# stm32.net
KiCad netlist of a schematic drawn in Altium Designer
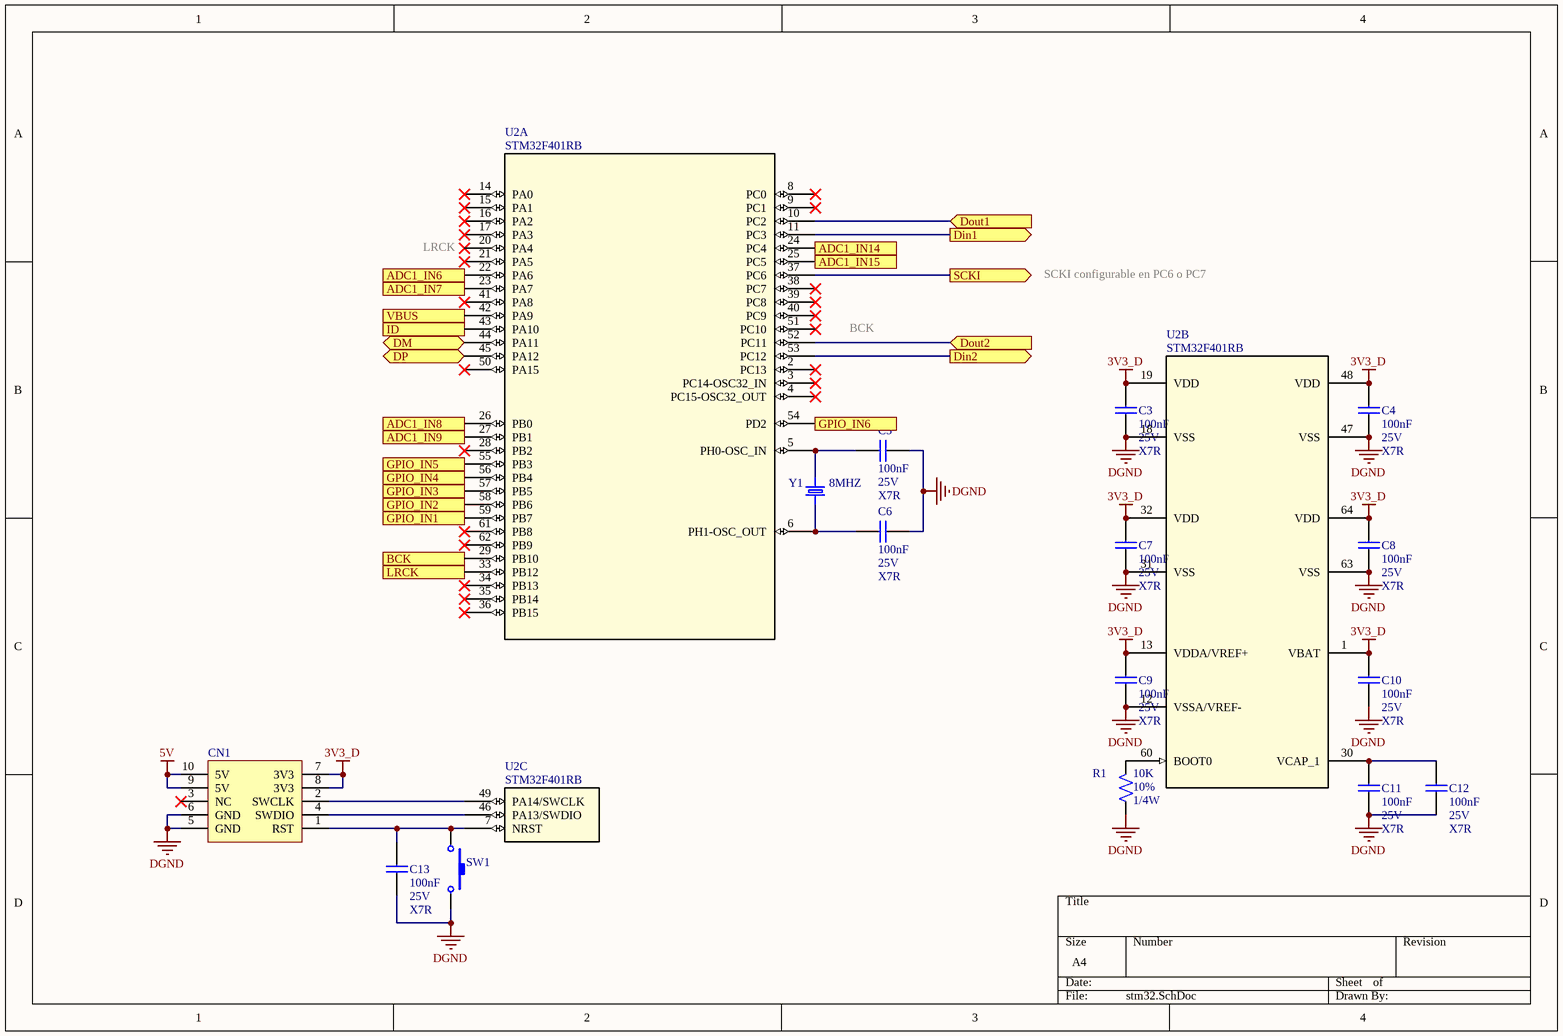
[diagram p0: stm32.SchDoc]

(export (version "E")
  (design (tool "Eeschema 10.0.6"))
  (components
    (comp (ref "C3")
      (value "Capacitor")
      (footprint "C0805")
      (description "Capacitor de placas paralelas")
      (fields (field (name "VALOR") "100nF") (field (name "TENSION") "25V") (field (name "TOLERANCIA") "X7R"))
      (libsource (lib "Sch_Comunes") (part "Capacitor"))
    )
    (comp (ref "C4")
      (value "Capacitor")
      (footprint "C0805")
      (description "Capacitor de placas paralelas")
      (fields (field (name "VALOR") "100nF") (field (name "TENSION") "25V") (field (name "TOLERANCIA") "X7R"))
      (libsource (lib "Sch_Comunes") (part "Capacitor"))
    )
    (comp (ref "C5")
      (value "Capacitor")
      (footprint "C0805")
      (description "Capacitor de placas paralelas")
      (fields (field (name "VALOR") "100nF") (field (name "TENSION") "25V") (field (name "TOLERANCIA") "X7R"))
      (libsource (lib "Sch_Comunes") (part "Capacitor"))
    )
    (comp (ref "C6")
      (value "Capacitor")
      (footprint "C0805")
      (description "Capacitor de placas paralelas")
      (fields (field (name "VALOR") "100nF") (field (name "TENSION") "25V") (field (name "TOLERANCIA") "X7R"))
      (libsource (lib "Sch_Comunes") (part "Capacitor"))
    )
    (comp (ref "C7")
      (value "Capacitor")
      (footprint "C0805")
      (description "Capacitor de placas paralelas")
      (fields (field (name "VALOR") "100nF") (field (name "TENSION") "25V") (field (name "TOLERANCIA") "X7R"))
      (libsource (lib "Sch_Comunes") (part "Capacitor"))
    )
    (comp (ref "C8")
      (value "Capacitor")
      (footprint "C0805")
      (description "Capacitor de placas paralelas")
      (fields (field (name "VALOR") "100nF") (field (name "TENSION") "25V") (field (name "TOLERANCIA") "X7R"))
      (libsource (lib "Sch_Comunes") (part "Capacitor"))
    )
    (comp (ref "C9")
      (value "Capacitor")
      (footprint "C0805")
      (description "Capacitor de placas paralelas")
      (fields (field (name "VALOR") "100nF") (field (name "TENSION") "25V") (field (name "TOLERANCIA") "X7R"))
      (libsource (lib "Sch_Comunes") (part "Capacitor"))
    )
    (comp (ref "C10")
      (value "Capacitor")
      (footprint "C0805")
      (description "Capacitor de placas paralelas")
      (fields (field (name "VALOR") "100nF") (field (name "TENSION") "25V") (field (name "TOLERANCIA") "X7R"))
      (libsource (lib "Sch_Comunes") (part "Capacitor"))
    )
    (comp (ref "C11")
      (value "Capacitor")
      (footprint "C0805")
      (description "Capacitor de placas paralelas")
      (fields (field (name "VALOR") "100nF") (field (name "TENSION") "25V") (field (name "TOLERANCIA") "X7R"))
      (libsource (lib "Sch_Comunes") (part "Capacitor"))
    )
    (comp (ref "C12")
      (value "Capacitor")
      (footprint "C0805")
      (description "Capacitor de placas paralelas")
      (fields (field (name "VALOR") "100nF") (field (name "TENSION") "25V") (field (name "TOLERANCIA") "X7R"))
      (libsource (lib "Sch_Comunes") (part "Capacitor"))
    )
    (comp (ref "C13")
      (value "Capacitor")
      (footprint "C0805")
      (description "Capacitor de placas paralelas")
      (fields (field (name "VALOR") "100nF") (field (name "TENSION") "25V") (field (name "TOLERANCIA") "X7R"))
      (libsource (lib "Sch_Comunes") (part "Capacitor"))
    )
    (comp (ref "CN1")
      (value "STLINK V2 Mini_2")
      (footprint "IDC10M")
      (description "STLINK V2 Mini")
      (libsource (lib "sch_STM32F401RB") (part "STLINK V2 Mini_2"))
    )
    (comp (ref "R1")
      (value "Resistor")
      (footprint "R0805")
      (description "Resistencia")
      (fields (field (name "VALOR") "10K") (field (name "POTENCIA") "1/4W") (field (name "TOLERANCIA") "10%"))
      (libsource (lib "sch_comunes") (part "Resistor"))
    )
    (comp (ref "SW1")
      (value "TAC_SWITCH_4")
      (footprint "TAC_SW_4")
      (description "Pulsador de 4 pines")
      (libsource (lib "sch_comunes") (part "TAC_SWITCH_4"))
    )
    (comp (ref "U2")
      (value "STM32F401RB")
      (footprint "LQFP64-10x10mm")
      (fields
        (field (name "MANUFACTURER_PART_NUMBER") "stm32f4xxr2")
        (field (name "MANUFACTURER") "STMicroelectronics")
      )
      (libsource (lib "sch_STM32F401RB") (part "STM32F4xxR2"))
    )
    (comp (ref "Y1")
      (value "XTAL")
      (footprint "XTAL_HC49/US_HS")
      (description "Resonador cerámico")
      (fields (field (name "FRECUENCIA") "8MHZ"))
      (libsource (lib "sch_STM32F401RB") (part "XTAL"))
    )
  )
  (nets
    (net (code "1") (name "/ADC1_IN6") (class "Default")
      (node (ref "U2") (pin "22") (pinfunction "PA6_22") (pintype "bidirectional"))
    )
    (net (code "2") (name "/ADC1_IN7") (class "Default")
      (node (ref "U2") (pin "23") (pinfunction "PA7_23") (pintype "bidirectional"))
    )
    (net (code "3") (name "/ADC1_IN8") (class "Default")
      (node (ref "U2") (pin "26") (pinfunction "PB0_26") (pintype "bidirectional"))
    )
    (net (code "4") (name "/ADC1_IN9") (class "Default")
      (node (ref "U2") (pin "27") (pinfunction "PB1_27") (pintype "bidirectional"))
    )
    (net (code "5") (name "/ADC1_IN14") (class "Default")
      (node (ref "U2") (pin "24") (pinfunction "PC4_24") (pintype "bidirectional"))
    )
    (net (code "6") (name "/ADC1_IN15") (class "Default")
      (node (ref "U2") (pin "25") (pinfunction "PC5_25") (pintype "bidirectional"))
    )
    (net (code "7") (name "/BCK") (class "Default")
      (node (ref "U2") (pin "29") (pinfunction "PB10_29") (pintype "bidirectional"))
    )
    (net (code "8") (name "/DM") (class "Default")
      (node (ref "U2") (pin "44") (pinfunction "PA11_44") (pintype "bidirectional"))
    )
    (net (code "9") (name "/DP") (class "Default")
      (node (ref "U2") (pin "45") (pinfunction "PA12_45") (pintype "bidirectional"))
    )
    (net (code "10") (name "/Din1") (class "Default")
      (node (ref "U2") (pin "11") (pinfunction "PC3_11") (pintype "bidirectional"))
    )
    (net (code "11") (name "/Din2") (class "Default")
      (node (ref "U2") (pin "53") (pinfunction "PC12_53") (pintype "bidirectional"))
    )
    (net (code "12") (name "/Dout1") (class "Default")
      (node (ref "U2") (pin "10") (pinfunction "PC2_10") (pintype "bidirectional"))
    )
    (net (code "13") (name "/Dout2") (class "Default")
      (node (ref "U2") (pin "52") (pinfunction "PC11_52") (pintype "bidirectional"))
    )
    (net (code "14") (name "/GPIO_IN1") (class "Default")
      (node (ref "U2") (pin "59") (pinfunction "PB7_59") (pintype "bidirectional"))
    )
    (net (code "15") (name "/GPIO_IN2") (class "Default")
      (node (ref "U2") (pin "58") (pinfunction "PB6_58") (pintype "bidirectional"))
    )
    (net (code "16") (name "/GPIO_IN3") (class "Default")
      (node (ref "U2") (pin "57") (pinfunction "PB5_57") (pintype "bidirectional"))
    )
    (net (code "17") (name "/GPIO_IN4") (class "Default")
      (node (ref "U2") (pin "56") (pinfunction "PB4_56") (pintype "bidirectional"))
    )
    (net (code "18") (name "/GPIO_IN5") (class "Default")
      (node (ref "U2") (pin "55") (pinfunction "PB3_55") (pintype "bidirectional"))
    )
    (net (code "19") (name "/GPIO_IN6") (class "Default")
      (node (ref "U2") (pin "54") (pinfunction "PD2_54") (pintype "bidirectional"))
    )
    (net (code "20") (name "/ID") (class "Default")
      (node (ref "U2") (pin "43") (pinfunction "PA10_43") (pintype "bidirectional"))
    )
    (net (code "21") (name "/LRCK") (class "Default")
      (node (ref "U2") (pin "33") (pinfunction "PB12_33") (pintype "bidirectional"))
    )
    (net (code "22") (name "/SCKI") (class "Default")
      (node (ref "U2") (pin "37") (pinfunction "PC6_37") (pintype "bidirectional"))
    )
    (net (code "23") (name "/VBUS") (class "Default")
      (node (ref "U2") (pin "42") (pinfunction "PA9_42") (pintype "bidirectional"))
    )
    (net (code "24") (name "3V3_D") (class "Default")
      (node (ref "C10") (pin "1") (pinfunction "1_1") (pintype "passive"))
      (node (ref "C3") (pin "1") (pinfunction "1_1") (pintype "passive"))
      (node (ref "C4") (pin "1") (pinfunction "1_1") (pintype "passive"))
      (node (ref "C7") (pin "1") (pinfunction "1_1") (pintype "passive"))
      (node (ref "C8") (pin "1") (pinfunction "1_1") (pintype "passive"))
      (node (ref "C9") (pin "1") (pinfunction "1_1") (pintype "passive"))
      (node (ref "CN1") (pin "7") (pinfunction "3V3_7") (pintype "passive"))
      (node (ref "CN1") (pin "8") (pinfunction "3V3_8") (pintype "passive"))
      (node (ref "U2") (pin "1") (pinfunction "VBAT_1") (pintype "power_in"))
      (node (ref "U2") (pin "13") (pinfunction "VDDA/VREF+_13") (pintype "power_in"))
      (node (ref "U2") (pin "19") (pinfunction "VDD_19") (pintype "power_in"))
      (node (ref "U2") (pin "32") (pinfunction "VDD_32") (pintype "power_in"))
      (node (ref "U2") (pin "48") (pinfunction "VDD_48") (pintype "power_in"))
      (node (ref "U2") (pin "64") (pinfunction "VDD_64") (pintype "power_in"))
    )
    (net (code "25") (name "5V") (class "Default")
      (node (ref "CN1") (pin "10") (pinfunction "5V_10") (pintype "passive"))
      (node (ref "CN1") (pin "9") (pinfunction "5V_9") (pintype "passive"))
    )
    (net (code "26") (name "DGND") (class "Default")
      (node (ref "C10") (pin "2") (pinfunction "2_2") (pintype "passive"))
      (node (ref "C11") (pin "2") (pinfunction "2_2") (pintype "passive"))
      (node (ref "C12") (pin "2") (pinfunction "2_2") (pintype "passive"))
      (node (ref "C13") (pin "2") (pinfunction "2_2") (pintype "passive"))
      (node (ref "C3") (pin "2") (pinfunction "2_2") (pintype "passive"))
      (node (ref "C4") (pin "2") (pinfunction "2_2") (pintype "passive"))
      (node (ref "C5") (pin "1") (pinfunction "1_1") (pintype "passive"))
      (node (ref "C6") (pin "1") (pinfunction "1_1") (pintype "passive"))
      (node (ref "C7") (pin "2") (pinfunction "2_2") (pintype "passive"))
      (node (ref "C8") (pin "2") (pinfunction "2_2") (pintype "passive"))
      (node (ref "C9") (pin "2") (pinfunction "2_2") (pintype "passive"))
      (node (ref "CN1") (pin "5") (pinfunction "GND_5") (pintype "passive"))
      (node (ref "CN1") (pin "6") (pinfunction "GND_6") (pintype "passive"))
      (node (ref "R1") (pin "1") (pinfunction "1_1") (pintype "passive"))
      (node (ref "SW1") (pin "2") (pinfunction "2_2") (pintype "passive"))
      (node (ref "U2") (pin "12") (pinfunction "VSSA/VREF-_12") (pintype "power_in"))
      (node (ref "U2") (pin "18") (pinfunction "VSS_18") (pintype "power_in"))
      (node (ref "U2") (pin "31") (pinfunction "VSS_31") (pintype "power_in"))
      (node (ref "U2") (pin "47") (pinfunction "VSS_47") (pintype "power_in"))
      (node (ref "U2") (pin "63") (pinfunction "VSS_63") (pintype "power_in"))
    )
    (net (code "27") (name "Net-(CN1-RST)") (class "Default")
      (node (ref "C13") (pin "1") (pinfunction "1_1") (pintype "passive"))
      (node (ref "CN1") (pin "1") (pinfunction "RST_1") (pintype "passive"))
      (node (ref "SW1") (pin "1") (pinfunction "1_1") (pintype "passive"))
      (node (ref "U2") (pin "7") (pinfunction "NRST_7") (pintype "bidirectional"))
    )
    (net (code "28") (name "Net-(CN1-SWCLK)") (class "Default")
      (node (ref "CN1") (pin "2") (pinfunction "SWCLK_2") (pintype "passive"))
      (node (ref "U2") (pin "49") (pinfunction "PA14/SWCLK_49") (pintype "bidirectional"))
    )
    (net (code "29") (name "Net-(CN1-SWDIO)") (class "Default")
      (node (ref "CN1") (pin "4") (pinfunction "SWDIO_4") (pintype "passive"))
      (node (ref "U2") (pin "46") (pinfunction "PA13/SWDIO_46") (pintype "bidirectional"))
    )
    (net (code "30") (name "Net-(U2A-PH0-OSC_IN)") (class "Default")
      (node (ref "C5") (pin "2") (pinfunction "2_2") (pintype "passive"))
      (node (ref "U2") (pin "5") (pinfunction "PH0-OSC_IN_5") (pintype "bidirectional"))
      (node (ref "Y1") (pin "1") (pinfunction "1_1") (pintype "passive"))
    )
    (net (code "31") (name "Net-(U2A-PH1-OSC_OUT)") (class "Default")
      (node (ref "C6") (pin "2") (pinfunction "2_2") (pintype "passive"))
      (node (ref "U2") (pin "6") (pinfunction "PH1-OSC_OUT_6") (pintype "bidirectional"))
      (node (ref "Y1") (pin "2") (pinfunction "2_2") (pintype "passive"))
    )
    (net (code "32") (name "Net-(U2B-BOOT0)") (class "Default")
      (node (ref "R1") (pin "2") (pinfunction "2_2") (pintype "passive"))
      (node (ref "U2") (pin "60") (pinfunction "BOOT0_60") (pintype "input"))
    )
    (net (code "33") (name "Net-(U2B-VCAP_1)") (class "Default")
      (node (ref "C11") (pin "1") (pinfunction "1_1") (pintype "passive"))
      (node (ref "C12") (pin "1") (pinfunction "1_1") (pintype "passive"))
      (node (ref "U2") (pin "30") (pinfunction "VCAP_1_30") (pintype "power_in"))
    )
    (net (code "34") (name "unconnected-(CN1-NC-Pad3)") (class "Default")
      (node (ref "CN1") (pin "3") (pinfunction "NC_3") (pintype "passive+no_connect"))
    )
    (net (code "35") (name "unconnected-(U2A-PA0-Pad14)") (class "Default")
      (node (ref "U2") (pin "14") (pinfunction "PA0_14") (pintype "bidirectional+no_connect"))
    )
    (net (code "36") (name "unconnected-(U2A-PA1-Pad15)") (class "Default")
      (node (ref "U2") (pin "15") (pinfunction "PA1_15") (pintype "bidirectional+no_connect"))
    )
    (net (code "37") (name "unconnected-(U2A-PA2-Pad16)") (class "Default")
      (node (ref "U2") (pin "16") (pinfunction "PA2_16") (pintype "bidirectional+no_connect"))
    )
    (net (code "38") (name "unconnected-(U2A-PA3-Pad17)") (class "Default")
      (node (ref "U2") (pin "17") (pinfunction "PA3_17") (pintype "bidirectional+no_connect"))
    )
    (net (code "39") (name "unconnected-(U2A-PA4-Pad20)") (class "Default")
      (node (ref "U2") (pin "20") (pinfunction "PA4_20") (pintype "bidirectional+no_connect"))
    )
    (net (code "40") (name "unconnected-(U2A-PA5-Pad21)") (class "Default")
      (node (ref "U2") (pin "21") (pinfunction "PA5_21") (pintype "bidirectional+no_connect"))
    )
    (net (code "41") (name "unconnected-(U2A-PA8-Pad41)") (class "Default")
      (node (ref "U2") (pin "41") (pinfunction "PA8_41") (pintype "bidirectional+no_connect"))
    )
    (net (code "42") (name "unconnected-(U2A-PA15-Pad50)") (class "Default")
      (node (ref "U2") (pin "50") (pinfunction "PA15_50") (pintype "bidirectional+no_connect"))
    )
    (net (code "43") (name "unconnected-(U2A-PB2-Pad28)") (class "Default")
      (node (ref "U2") (pin "28") (pinfunction "PB2_28") (pintype "bidirectional+no_connect"))
    )
    (net (code "44") (name "unconnected-(U2A-PB8-Pad61)") (class "Default")
      (node (ref "U2") (pin "61") (pinfunction "PB8_61") (pintype "bidirectional+no_connect"))
    )
    (net (code "45") (name "unconnected-(U2A-PB9-Pad62)") (class "Default")
      (node (ref "U2") (pin "62") (pinfunction "PB9_62") (pintype "bidirectional+no_connect"))
    )
    (net (code "46") (name "unconnected-(U2A-PB13-Pad34)") (class "Default")
      (node (ref "U2") (pin "34") (pinfunction "PB13_34") (pintype "bidirectional+no_connect"))
    )
    (net (code "47") (name "unconnected-(U2A-PB14-Pad35)") (class "Default")
      (node (ref "U2") (pin "35") (pinfunction "PB14_35") (pintype "bidirectional+no_connect"))
    )
    (net (code "48") (name "unconnected-(U2A-PB15-Pad36)") (class "Default")
      (node (ref "U2") (pin "36") (pinfunction "PB15_36") (pintype "bidirectional+no_connect"))
    )
    (net (code "49") (name "unconnected-(U2A-PC0-Pad8)") (class "Default")
      (node (ref "U2") (pin "8") (pinfunction "PC0_8") (pintype "bidirectional+no_connect"))
    )
    (net (code "50") (name "unconnected-(U2A-PC1-Pad9)") (class "Default")
      (node (ref "U2") (pin "9") (pinfunction "PC1_9") (pintype "bidirectional+no_connect"))
    )
    (net (code "51") (name "unconnected-(U2A-PC7-Pad38)") (class "Default")
      (node (ref "U2") (pin "38") (pinfunction "PC7_38") (pintype "bidirectional+no_connect"))
    )
    (net (code "52") (name "unconnected-(U2A-PC8-Pad39)") (class "Default")
      (node (ref "U2") (pin "39") (pinfunction "PC8_39") (pintype "bidirectional+no_connect"))
    )
    (net (code "53") (name "unconnected-(U2A-PC9-Pad40)") (class "Default")
      (node (ref "U2") (pin "40") (pinfunction "PC9_40") (pintype "bidirectional+no_connect"))
    )
    (net (code "54") (name "unconnected-(U2A-PC10-Pad51)") (class "Default")
      (node (ref "U2") (pin "51") (pinfunction "PC10_51") (pintype "bidirectional+no_connect"))
    )
    (net (code "55") (name "unconnected-(U2A-PC13-Pad2)") (class "Default")
      (node (ref "U2") (pin "2") (pinfunction "PC13_2") (pintype "bidirectional+no_connect"))
    )
    (net (code "56") (name "unconnected-(U2A-PC14-OSC32_IN-Pad3)") (class "Default")
      (node (ref "U2") (pin "3") (pinfunction "PC14-OSC32_IN_3") (pintype "bidirectional+no_connect"))
    )
    (net (code "57") (name "unconnected-(U2A-PC15-OSC32_OUT-Pad4)") (class "Default")
      (node (ref "U2") (pin "4") (pinfunction "PC15-OSC32_OUT_4") (pintype "bidirectional+no_connect"))
    )
  )
)
